# YA-N-Power_Supply.net
KiCad netlist of a schematic drawn in Altium Designer
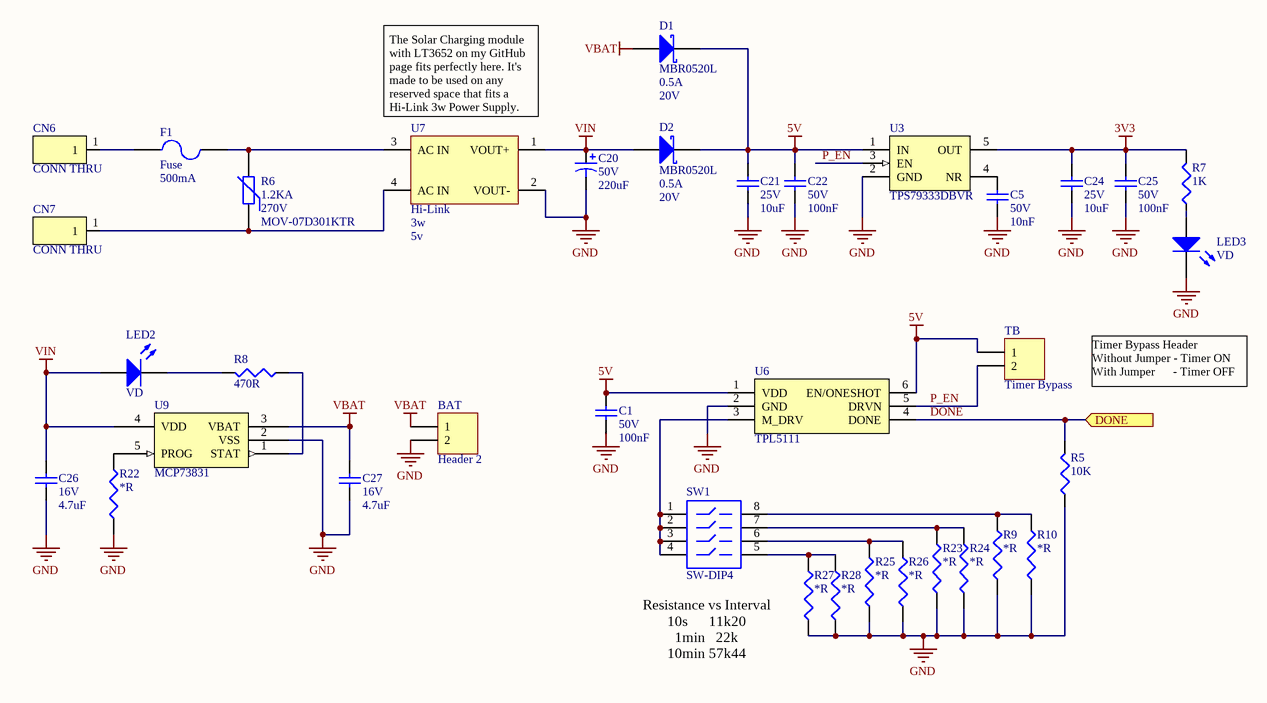
[diagram p0: YA-N-Power_Supply.SchDoc]

(export (version "E")
  (design (tool "Eeschema 10.0.6"))
  (components
    (comp (ref "BAT")
      (value "Header 2")
      (footprint "CONN XH2.54 - 2")
      (description "Header, 2-Pin")
      (libsource (lib "NavarroCON") (part "Header 2"))
    )
    (comp (ref "C1")
      (value "100nF")
      (footprint "CC0603")
      (description "Capacitor (Semiconductor SIM Model)")
      (fields (field (name "TENSÃO") "50V") (field (name "Comment") "Capacitor Cerâmico"))
      (libsource (lib "NavarroCAP") (part "Cap 100nF 50V 0603 X7R"))
    )
    (comp (ref "C5")
      (value "10nF")
      (footprint "CC0603")
      (description "Capacitor (Semiconductor SIM Model)")
      (fields (field (name "TENSÃO") "50V") (field (name "Comment") "Capacitor Cerâmico"))
      (libsource (lib "NavarroCAP") (part "Cap 10nF 50V 0603 X7R 5%"))
    )
    (comp (ref "C20")
      (value "220uF")
      (footprint "CPOLRAD10X20")
      (description "Polarized Capacitor")
      (fields (field (name "TENSÃO") "50V") (field (name "Comment") "Capacitor Aluminio"))
      (libsource (lib "NavarroCAP") (part "PCap 220uF 50V CPOLRAD10X20 LOESR"))
    )
    (comp (ref "C21")
      (value "10uF")
      (footprint "CC0805")
      (description "Capacitor (Semiconductor SIM Model)")
      (fields (field (name "TENSÃO") "25V") (field (name "Comment") "Capacitor Cerâmico"))
      (libsource (lib "NavarroCAP") (part "Cap 10uF 25V 0805 X5R"))
    )
    (comp (ref "C22")
      (value "100nF")
      (footprint "CC0603")
      (description "Capacitor (Semiconductor SIM Model)")
      (fields (field (name "TENSÃO") "50V") (field (name "Comment") "Capacitor Cerâmico"))
      (libsource (lib "NavarroCAP") (part "Cap 100nF 50V 0603 X7R"))
    )
    (comp (ref "C24")
      (value "10uF")
      (footprint "CC0805")
      (description "Capacitor (Semiconductor SIM Model)")
      (fields (field (name "TENSÃO") "25V") (field (name "Comment") "Capacitor Cerâmico"))
      (libsource (lib "NavarroCAP") (part "Cap 10uF 25V 0805 X5R"))
    )
    (comp (ref "C25")
      (value "100nF")
      (footprint "CC0603")
      (description "Capacitor (Semiconductor SIM Model)")
      (fields (field (name "TENSÃO") "50V") (field (name "Comment") "Capacitor Cerâmico"))
      (libsource (lib "NavarroCAP") (part "Cap 100nF 50V 0603 X7R"))
    )
    (comp (ref "C26")
      (value "4.7uF")
      (footprint "CC0805")
      (description "Capacitor (Semiconductor SIM Model)")
      (fields (field (name "TENSÃO") "16V") (field (name "Comment") "Capacitor Cerâmico"))
      (libsource (lib "NavarroCAP") (part "Cap 4.7uF 16V 0805 X5R"))
    )
    (comp (ref "C27")
      (value "4.7uF")
      (footprint "CC0805")
      (description "Capacitor (Semiconductor SIM Model)")
      (fields (field (name "TENSÃO") "16V") (field (name "Comment") "Capacitor Cerâmico"))
      (libsource (lib "NavarroCAP") (part "Cap 4.7uF 16V 0805 X5R"))
    )
    (comp (ref "CN6")
      (value "CONN THRU")
      (footprint "CONN THRU")
      (libsource (lib "NavarroCON") (part "CONN THRU"))
    )
    (comp (ref "CN7")
      (value "CONN THRU")
      (footprint "CONN THRU")
      (libsource (lib "NavarroCON") (part "CONN THRU"))
    )
    (comp (ref "D1")
      (value "MBR0520L")
      (footprint "SOD-123F")
      (description "Schottky Diode")
      (fields (field (name "CORRENTE") "0.5A") (field (name "TENSÃO") "20V"))
      (libsource (lib "NavarroSEMI") (part "DS 20V 0.5A 385mV SOD-123"))
    )
    (comp (ref "D2")
      (value "MBR0520L")
      (footprint "SOD-123F")
      (description "Schottky Diode")
      (fields (field (name "CORRENTE") "0.5A") (field (name "TENSÃO") "20V"))
      (libsource (lib "NavarroSEMI") (part "DS 20V 0.5A 385mV SOD-123"))
    )
    (comp (ref "F1")
      (value "Fuse")
      (footprint "BLOCKFUS_4X8")
      (fields (field (name "CORRENTE") "500mA"))
      (libsource (lib "Navarro") (part "Fuse Disc"))
    )
    (comp (ref "LED2")
      (value "VD")
      (footprint "LED 0603")
      (description "LED")
      (libsource (lib "NavarroSEMI") (part "LED 0603 VD 2V 75mW"))
    )
    (comp (ref "LED3")
      (value "VD")
      (footprint "LED 0603")
      (description "LED")
      (libsource (lib "NavarroSEMI") (part "LED 0603 VD 2V 75mW"))
    )
    (comp (ref "R5")
      (value "10K")
      (footprint "CC0603")
      (description "Resistor")
      (libsource (lib "NavarroRES") (part "Res 10K 1% 0603 1/10W"))
    )
    (comp (ref "R6")
      (value "270V")
      (footprint "DISCFUS7")
      (description "Varistor (Voltage-Sensitive Resistor)")
      (fields
        (field (name "CORRENTE") "1.2KA")
        (field (name "OBS") "MOV-07D301KTR")
        (field (name "Comment") "Varistor")
      )
      (libsource (lib "NavarroRES") (part "Var 270V 1.2KA Disc7mm"))
    )
    (comp (ref "R7")
      (value "1K")
      (footprint "CC0603")
      (description "Resistor")
      (libsource (lib "NavarroRES") (part "Res 1K 1% 0603 1/10W"))
    )
    (comp (ref "R8")
      (value "470R")
      (footprint "CC0603")
      (description "Resistor")
      (libsource (lib "NavarroRES") (part "Res 470R 5% 0603 1/10W"))
    )
    (comp (ref "R9")
      (value "*R")
      (footprint "CC0603")
      (description "Resistor")
      (libsource (lib "NavarroRES") (part "Res - $Val $% $Footprint $Pot"))
    )
    (comp (ref "R10")
      (value "*R")
      (footprint "CC0603")
      (description "Resistor")
      (libsource (lib "NavarroRES") (part "Res - $Val $% $Footprint $Pot"))
    )
    (comp (ref "R22")
      (value "*R")
      (footprint "CC0603")
      (description "Resistor")
      (libsource (lib "NavarroRES") (part "Res - $Val $% $Footprint $Pot"))
    )
    (comp (ref "R23")
      (value "*R")
      (footprint "CC0603")
      (description "Resistor")
      (libsource (lib "NavarroRES") (part "Res - $Val $% $Footprint $Pot"))
    )
    (comp (ref "R24")
      (value "*R")
      (footprint "CC0603")
      (description "Resistor")
      (libsource (lib "NavarroRES") (part "Res - $Val $% $Footprint $Pot"))
    )
    (comp (ref "R25")
      (value "*R")
      (footprint "CC0603")
      (description "Resistor")
      (libsource (lib "NavarroRES") (part "Res - $Val $% $Footprint $Pot"))
    )
    (comp (ref "R26")
      (value "*R")
      (footprint "CC0603")
      (description "Resistor")
      (libsource (lib "NavarroRES") (part "Res - $Val $% $Footprint $Pot"))
    )
    (comp (ref "R27")
      (value "*R")
      (footprint "CC0603")
      (description "Resistor")
      (libsource (lib "NavarroRES") (part "Res - $Val $% $Footprint $Pot"))
    )
    (comp (ref "R28")
      (value "*R")
      (footprint "CC0603")
      (description "Resistor")
      (libsource (lib "NavarroRES") (part "Res - $Val $% $Footprint $Pot"))
    )
    (comp (ref "SW1")
      (value "SW-DIP4")
      (footprint "SWITCH-DIP8")
      (description "4009 Series DIP Switch, Raised actuator")
      (libsource (lib "Navarro") (part "SW-DIP4"))
    )
    (comp (ref "TB")
      (value "Timer Bypass")
      (footprint "CONN HDR1X2")
      (description "Header, 2-Pin")
      (libsource (lib "NavarroCON") (part "Header 2"))
    )
    (comp (ref "U3")
      (value "TPS79333DBVR")
      (footprint "SOT-23-5N")
      (description "ULTRALOW-NOISE, HIGH PSRR, FAST RF 200mA LOW-DROPOUT LINEAR  REGULATORS I")
      (libsource (lib "Navarro") (part "TPS79333"))
    )
    (comp (ref "U6")
      (value "TPL5111")
      (footprint "TSOT-23-6N")
      (description "Nano-Power System Timer for Power Gating")
      (libsource (lib "Navarro") (part "TPL5111"))
    )
    (comp (ref "U7")
      (value "Hi-Link")
      (footprint "Fonte-HILINK")
      (description "Fonte chaveada isolada")
      (fields (field (name "POTÊNCIA") "3w") (field (name "TENSÃO") "5v"))
      (libsource (lib "Navarro") (part "Fonte Hi-Link"))
    )
    (comp (ref "U9")
      (value "MCP73831")
      (footprint "SOT-23-5N")
      (description "Miniature Single-Cell, Fully Integrated Li-Ion, Li-Polymer Charge Management Controllers")
      (libsource (lib "Navarro") (part "MCP73832/1"))
    )
  )
  (nets
    (net (code "1") (name "/DONE") (class "Default")
      (node (ref "R5") (pin "2") (pinfunction "2_2") (pintype "passive"))
      (node (ref "U6") (pin "4") (pinfunction "DONE_4") (pintype "passive"))
    )
    (net (code "2") (name "/P_EN") (class "Default")
      (node (ref "TB") (pin "2") (pinfunction "2_2") (pintype "passive"))
      (node (ref "U3") (pin "3") (pinfunction "EN_3") (pintype "input"))
      (node (ref "U6") (pin "5") (pinfunction "DRVN_5") (pintype "passive"))
    )
    (net (code "3") (name "3V3") (class "Default")
      (node (ref "C24") (pin "2") (pinfunction "2_2") (pintype "passive"))
      (node (ref "C25") (pin "2") (pinfunction "2_2") (pintype "passive"))
      (node (ref "R7") (pin "2") (pinfunction "2_2") (pintype "passive"))
      (node (ref "U3") (pin "5") (pinfunction "OUT_5") (pintype "power_in"))
    )
    (net (code "4") (name "5V") (class "Default")
      (node (ref "C1") (pin "2") (pinfunction "2_2") (pintype "passive"))
      (node (ref "C21") (pin "2") (pinfunction "2_2") (pintype "passive"))
      (node (ref "C22") (pin "2") (pinfunction "2_2") (pintype "passive"))
      (node (ref "D1") (pin "2") (pinfunction "K_2") (pintype "passive"))
      (node (ref "D2") (pin "2") (pinfunction "K_2") (pintype "passive"))
      (node (ref "TB") (pin "1") (pinfunction "1_1") (pintype "passive"))
      (node (ref "U3") (pin "1") (pinfunction "IN_1") (pintype "power_in"))
      (node (ref "U6") (pin "1") (pinfunction "VDD_1") (pintype "power_in"))
      (node (ref "U6") (pin "6") (pinfunction "EN/ONESHOT_6") (pintype "passive"))
    )
    (net (code "5") (name "GND") (class "Default")
      (node (ref "BAT") (pin "2") (pinfunction "2_2") (pintype "passive"))
      (node (ref "C1") (pin "1") (pinfunction "1_1") (pintype "passive"))
      (node (ref "C20") (pin "2") (pinfunction "2_2") (pintype "passive"))
      (node (ref "C21") (pin "1") (pinfunction "1_1") (pintype "passive"))
      (node (ref "C22") (pin "1") (pinfunction "1_1") (pintype "passive"))
      (node (ref "C24") (pin "1") (pinfunction "1_1") (pintype "passive"))
      (node (ref "C25") (pin "1") (pinfunction "1_1") (pintype "passive"))
      (node (ref "C26") (pin "1") (pinfunction "1_1") (pintype "passive"))
      (node (ref "C27") (pin "1") (pinfunction "1_1") (pintype "passive"))
      (node (ref "C5") (pin "1") (pinfunction "1_1") (pintype "passive"))
      (node (ref "LED3") (pin "2") (pinfunction "K_2") (pintype "passive"))
      (node (ref "R10") (pin "1") (pinfunction "1_1") (pintype "passive"))
      (node (ref "R22") (pin "1") (pinfunction "1_1") (pintype "passive"))
      (node (ref "R23") (pin "1") (pinfunction "1_1") (pintype "passive"))
      (node (ref "R24") (pin "1") (pinfunction "1_1") (pintype "passive"))
      (node (ref "R25") (pin "1") (pinfunction "1_1") (pintype "passive"))
      (node (ref "R26") (pin "1") (pinfunction "1_1") (pintype "passive"))
      (node (ref "R27") (pin "1") (pinfunction "1_1") (pintype "passive"))
      (node (ref "R28") (pin "1") (pinfunction "1_1") (pintype "passive"))
      (node (ref "R5") (pin "1") (pinfunction "1_1") (pintype "passive"))
      (node (ref "R9") (pin "1") (pinfunction "1_1") (pintype "passive"))
      (node (ref "U3") (pin "2") (pinfunction "GND_2") (pintype "power_in"))
      (node (ref "U6") (pin "2") (pinfunction "GND_2") (pintype "power_in"))
      (node (ref "U7") (pin "2") (pinfunction "VOUT-_2") (pintype "power_in"))
      (node (ref "U9") (pin "2") (pinfunction "VSS_2") (pintype "power_in"))
    )
    (net (code "6") (name "Net-(CN6-Pad1)") (class "Default")
      (node (ref "CN6") (pin "1") (pinfunction "1_1") (pintype "tri_state"))
      (node (ref "F1") (pin "1") (pinfunction "1_1") (pintype "passive"))
    )
    (net (code "7") (name "Net-(CN7-Pad1)") (class "Default")
      (node (ref "CN7") (pin "1") (pinfunction "1_1") (pintype "tri_state"))
      (node (ref "R6") (pin "1") (pinfunction "1_1") (pintype "passive"))
      (node (ref "U7") (pin "4") (pinfunction "AC_IN_4") (pintype "power_in"))
    )
    (net (code "8") (name "Net-(F1-Pad2)") (class "Default")
      (node (ref "F1") (pin "2") (pinfunction "2_2") (pintype "passive"))
      (node (ref "R6") (pin "2") (pinfunction "2_2") (pintype "passive"))
      (node (ref "U7") (pin "3") (pinfunction "AC_IN_3") (pintype "power_in"))
    )
    (net (code "9") (name "Net-(LED2-K)") (class "Default")
      (node (ref "LED2") (pin "2") (pinfunction "K_2") (pintype "passive"))
      (node (ref "R8") (pin "2") (pinfunction "2_2") (pintype "passive"))
    )
    (net (code "10") (name "Net-(LED3-A)") (class "Default")
      (node (ref "LED3") (pin "1") (pinfunction "A_1") (pintype "passive"))
      (node (ref "R7") (pin "1") (pinfunction "1_1") (pintype "passive"))
    )
    (net (code "11") (name "Net-(R10-Pad2)") (class "Default")
      (node (ref "R10") (pin "2") (pinfunction "2_2") (pintype "passive"))
      (node (ref "R9") (pin "2") (pinfunction "2_2") (pintype "passive"))
      (node (ref "SW1") (pin "8") (pinfunction "8_8") (pintype "passive"))
    )
    (net (code "12") (name "Net-(R23-Pad2)") (class "Default")
      (node (ref "R23") (pin "2") (pinfunction "2_2") (pintype "passive"))
      (node (ref "R24") (pin "2") (pinfunction "2_2") (pintype "passive"))
      (node (ref "SW1") (pin "7") (pinfunction "7_7") (pintype "passive"))
    )
    (net (code "13") (name "Net-(R25-Pad2)") (class "Default")
      (node (ref "R25") (pin "2") (pinfunction "2_2") (pintype "passive"))
      (node (ref "R26") (pin "2") (pinfunction "2_2") (pintype "passive"))
      (node (ref "SW1") (pin "6") (pinfunction "6_6") (pintype "passive"))
    )
    (net (code "14") (name "Net-(R27-Pad2)") (class "Default")
      (node (ref "R27") (pin "2") (pinfunction "2_2") (pintype "passive"))
      (node (ref "R28") (pin "2") (pinfunction "2_2") (pintype "passive"))
      (node (ref "SW1") (pin "5") (pinfunction "5_5") (pintype "passive"))
    )
    (net (code "15") (name "Net-(U3-NR)") (class "Default")
      (node (ref "C5") (pin "2") (pinfunction "2_2") (pintype "passive"))
      (node (ref "U3") (pin "4") (pinfunction "NR_4") (pintype "passive"))
    )
    (net (code "16") (name "Net-(U6-M_DRV)") (class "Default")
      (node (ref "SW1") (pin "1") (pinfunction "1_1") (pintype "passive"))
      (node (ref "SW1") (pin "2") (pinfunction "2_2") (pintype "passive"))
      (node (ref "SW1") (pin "3") (pinfunction "3_3") (pintype "passive"))
      (node (ref "SW1") (pin "4") (pinfunction "4_4") (pintype "passive"))
      (node (ref "U6") (pin "3") (pinfunction "M_DRV_3") (pintype "passive"))
    )
    (net (code "17") (name "Net-(U9-PROG)") (class "Default")
      (node (ref "R22") (pin "2") (pinfunction "2_2") (pintype "passive"))
      (node (ref "U9") (pin "5") (pinfunction "PROG_5") (pintype "input"))
    )
    (net (code "18") (name "Net-(U9-STAT)") (class "Default")
      (node (ref "R8") (pin "1") (pinfunction "1_1") (pintype "passive"))
      (node (ref "U9") (pin "1") (pinfunction "STAT_1") (pintype "output"))
    )
    (net (code "19") (name "VBAT") (class "Default")
      (node (ref "BAT") (pin "1") (pinfunction "1_1") (pintype "passive"))
      (node (ref "C27") (pin "2") (pinfunction "2_2") (pintype "passive"))
      (node (ref "D1") (pin "1") (pinfunction "A_1") (pintype "passive"))
      (node (ref "U9") (pin "3") (pinfunction "VBAT_3") (pintype "power_in"))
    )
    (net (code "20") (name "VIN") (class "Default")
      (node (ref "C20") (pin "1") (pinfunction "1_1") (pintype "passive"))
      (node (ref "C26") (pin "2") (pinfunction "2_2") (pintype "passive"))
      (node (ref "D2") (pin "1") (pinfunction "A_1") (pintype "passive"))
      (node (ref "LED2") (pin "1") (pinfunction "A_1") (pintype "passive"))
      (node (ref "U7") (pin "1") (pinfunction "VOUT+_1") (pintype "power_in"))
      (node (ref "U9") (pin "4") (pinfunction "VDD_4") (pintype "power_in"))
    )
  )
)
